# USB-UART.net
KiCad netlist of a schematic drawn in Altium Designer
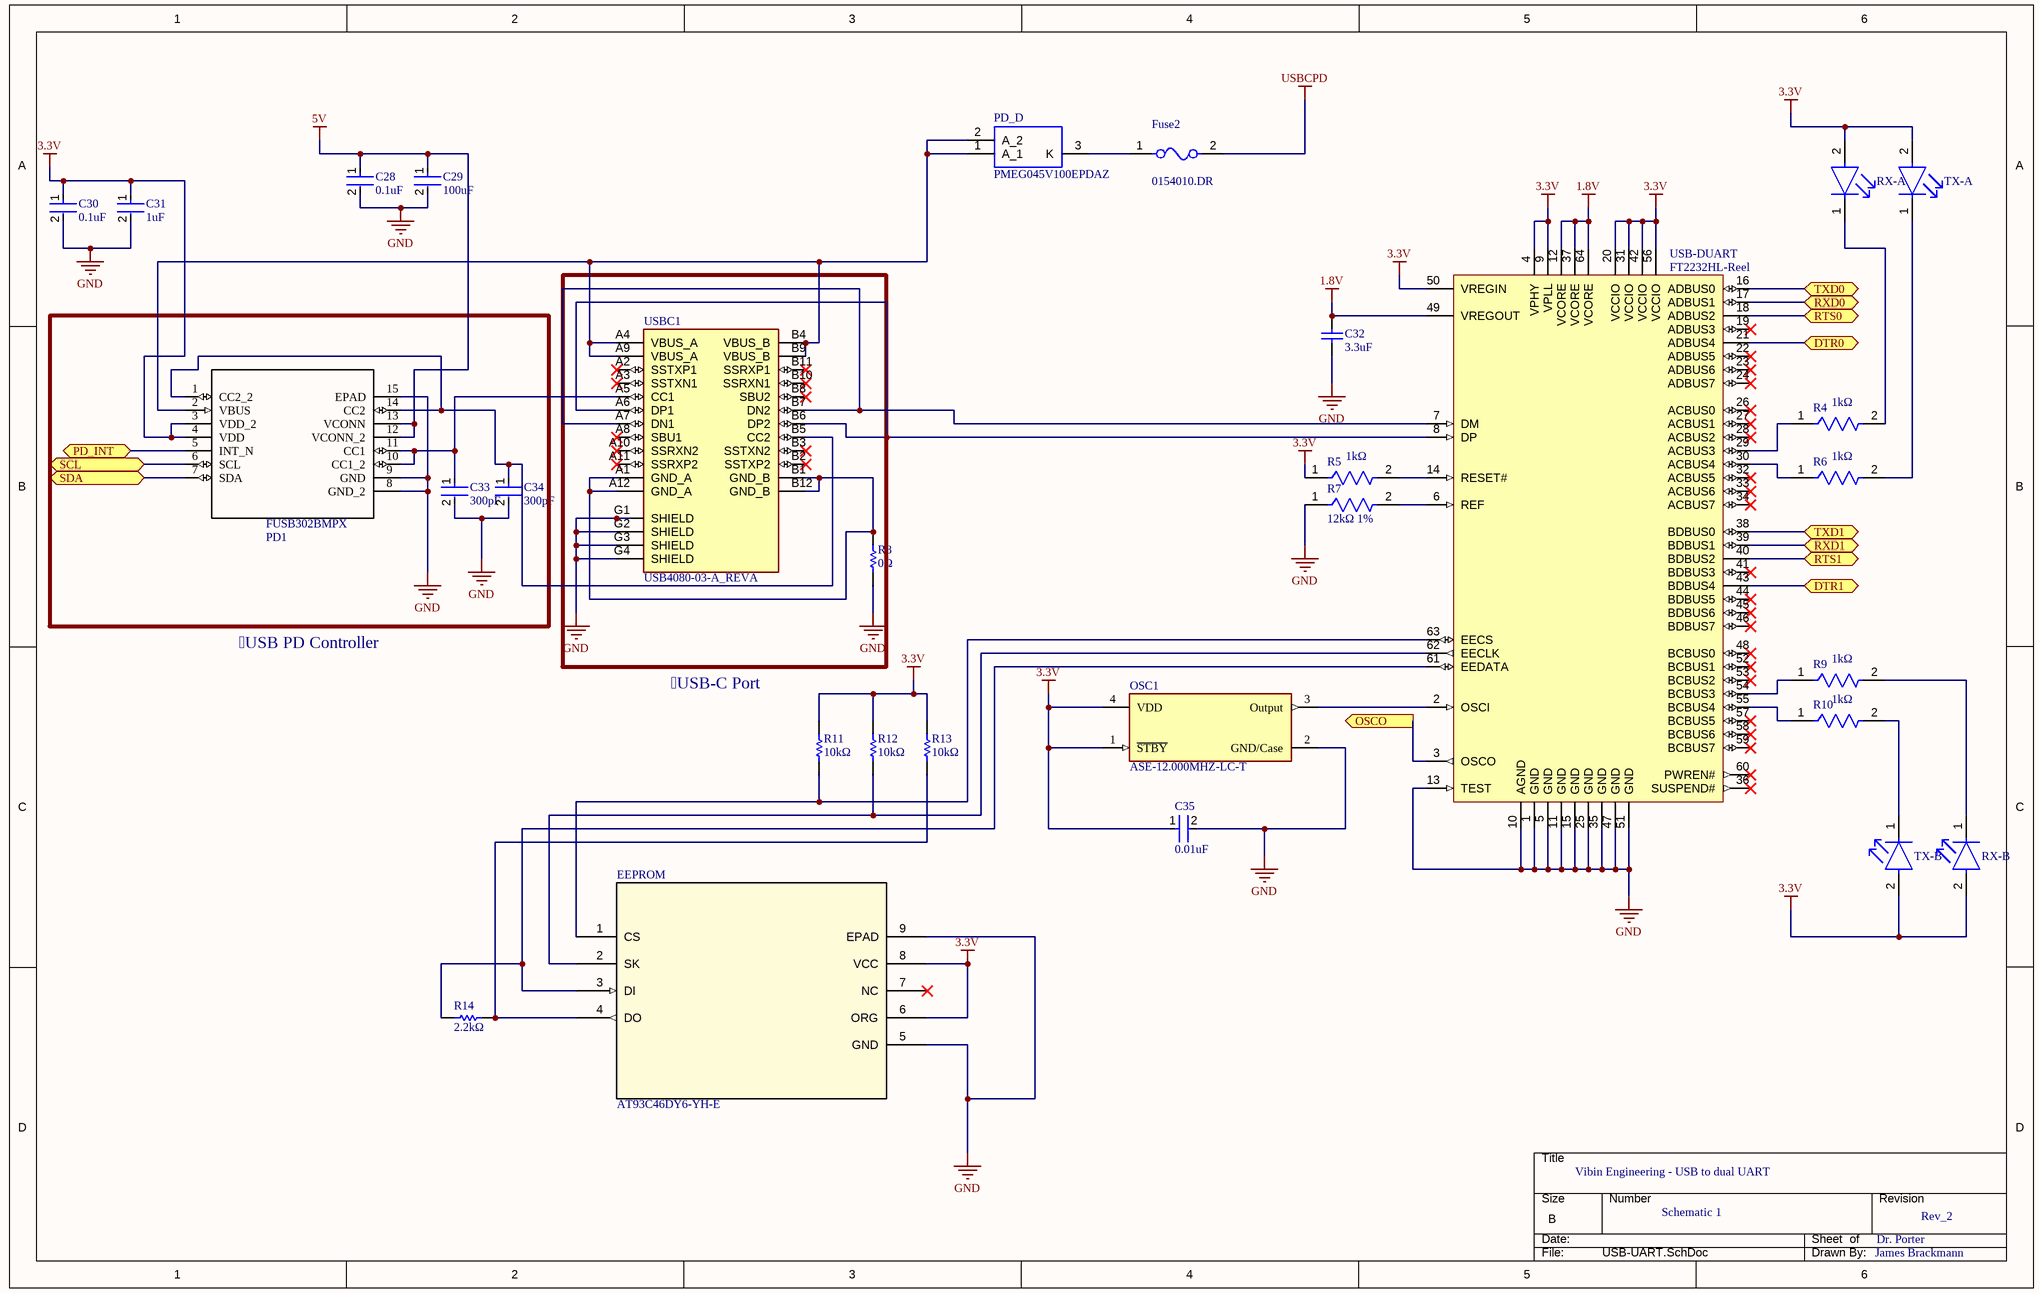
[diagram p0: USB-UART.SchDoc]

(export (version "E")
  (design (tool "Eeschema 10.0.6"))
  (components
    (comp (ref "C28")
      (value "0.1uF")
      (footprint "FP-C0603-CJ-MFG")
      (description "CAP CER 0.1UF 50V X7R 0603              C0603X104K5RACTU")
      (fields (field (name "MANUFACTURER PART NUMBER") "C0603X104K5RACTU") (field (name "VOLTAGE") "50V"))
      (libsource (lib "Altium Content Vault") (part "11868f565c42a9108669ba33697ecf6"))
    )
    (comp (ref "C29")
      (value "100uF")
      (footprint "FP-GRM32E-0_3-0_2-IPC_B")
      (fields (field (name "TOLERANCE") "20%") (field (name "VOLTAGE") "10V"))
      (libsource (lib "Altium Content Vault") (part "02cd4be3c70576c341d710602a673aa"))
    )
    (comp (ref "C30")
      (value "0.1uF")
      (footprint "FP-C0603-CJ-MFG")
      (description "CAP CER 0.1UF 50V X7R 0603              C0603X104K5RACTU")
      (fields (field (name "MANUFACTURER PART NUMBER") "C0603X104K5RACTU") (field (name "VOLTAGE") "50V"))
      (libsource (lib "Altium Content Vault") (part "11868f565c42a9108669ba33697ecf6"))
    )
    (comp (ref "C31")
      (value "1uF")
      (footprint "FP-C2012-125-0_2-IPC_A")
      (description "Multilayer Ceramic Capacitors 1μF ±10% 25V X5R SMD 0805           C2012X5R1E105K125AA")
      (fields (field (name "VOLTAGE") "25V") (field (name "TOLERANCE") "10%"))
      (libsource (lib "Altium Content Vault") (part "b4654b650e69147ec39a6b967a45e02"))
    )
    (comp (ref "C32")
      (value "3.3uF")
      (footprint "CAPC1210(3225)190_N")
      (description "CAP 3.3uF 50V ±10% 1210 (3225 Metric) Thickness 1.9mm SMD")
      (fields (field (name "TOLERANCE") "Â±10%"))
      (libsource (lib "Altium Content Vault") (part "CAP"))
    )
    (comp (ref "C33")
      (value "300pF")
      (footprint "FP-C0603C-CF-MFG")
      (description "CAP CER 300PF 50V 5% NP0 0603        C0603C301J5GACTU")
      (fields
        (field (name "TOLERANCE") "0.05")
        (field (name "OCTOPART") "https://octopart.com/c0603c301j5gactu-kemet-9143916")
      )
      (libsource (lib "Altium Content Vault") (part "b4654b650e69147ec39a6b967a45e02"))
    )
    (comp (ref "C34")
      (value "300pF")
      (footprint "FP-C0603C-CF-MFG")
      (description "CAP CER 300PF 50V 5% NP0 0603          C0603C301J5GACTU")
      (fields
        (field (name "TOLERANCE") "0.05")
        (field (name "OCTOPART") "https://octopart.com/c0603c301j5gactu-kemet-9143916")
      )
      (libsource (lib "Altium Content Vault") (part "b4654b650e69147ec39a6b967a45e02"))
    )
    (comp (ref "C35")
      (value "0.01uF")
      (footprint "FP-GRM219-0_1-IPC_B")
      (description "Chip Multilayer Ceramic Capacitors for General Purpose, 0805, 10000pF, C0G, 30ppm/°C, 5%, 50V")
      (fields (field (name "VOLTAGE") "50V") (field (name "TOLERANCE") "5%"))
      (libsource (lib "Altium Content Vault") (part "02cd4be3c70576c341d710602a673aa"))
    )
    (comp (ref "EEPROM")
      (value "AT93C46DY6-YH-E")
      (footprint "8Y6_MCH")
      (description "No Description Available")
      (fields (field (name "COPYRIGHT") "Copyright (C) 2022 Ultra Librarian. All rights reserved."))
      (libsource (lib "AT93C46DY6-YH-E") (part "AT93C46DY6-YH-E"))
    )
    (comp (ref "Fuse2")
      (value "0154010.DR")
      (footprint "FP-0154-MFG")
      (description "FUSE BRD MNT 10A 125VAC/VDC SMD    0154010.DR")
      (fields
        (field (name "MANUFACTURER") "Littelfuse Inc")
        (field (name "OCTOPART") "https://octopart.com/0154010.dr-littelfuse-565890")
      )
      (libsource (lib "Altium Content Vault") (part "5bcf9b9f640e542cf0359d10258e979"))
    )
    (comp (ref "OSC1")
      (value "ASE-12.000MHZ-LC-T")
      (footprint "FP-ASE-MFG")
      (description "XTAL Oscillator 12MHz ±50ppm CMOS 3.3V 4-SMD 3.2mm x 2.5mm")
      (libsource (lib "Altium Content Vault") (part "61a724e6190563596ac712fef61ad37"))
    )
    (comp (ref "PD1")
      (value "FUSB302BMPX")
      (footprint "*MLP14_2P5X2P5_ONS")
      (description "USB Controller USB 3.1 USB Interface 14-MLP (2.5x2.5)          FUSB302BMPX")
      (fields (field (name "MF") "ON Semiconductor"))
      (libsource (lib "FUSB302BMPX") (part "FUSB302BMPX"))
    )
    (comp (ref "PD_D")
      (value "PMEG045V100EPDAZ")
      (footprint "PMEG045V150EPDAZ")
      (description "Diode Schottky 45V 10A Surface Mount CFP15         PMEG045V100EPDAZ")
      (fields (field (name "MF") "Nexperia USA"))
      (libsource (lib "PMEG045V100EPDAZ") (part "PMEG045V100EPDAZ"))
    )
    (comp (ref "R4")
      (value "1kΩ")
      (footprint "FP-CRCW0603-e3-MFG")
      (description "RES Thick Film, 1kΩ, 1%, 0.1W, 100ppm/°C, 0603")
      (fields (field (name "TOLERANCE") "1%"))
      (libsource (lib "Altium Content Vault") (part "1029c3af85768c4190bb7ad29bc67b5"))
    )
    (comp (ref "R5")
      (value "1kΩ")
      (footprint "FP-CRCW0603-e3-MFG")
      (description "RES Thick Film, 1kΩ, 1%, 0.1W, 100ppm/°C, 0603")
      (fields (field (name "TOLERANCE") "1%"))
      (libsource (lib "Altium Content Vault") (part "1029c3af85768c4190bb7ad29bc67b5"))
    )
    (comp (ref "R6")
      (value "1kΩ")
      (footprint "FP-CRCW0603-e3-MFG")
      (description "RES Thick Film, 1kΩ, 1%, 0.1W, 100ppm/°C, 0603")
      (fields (field (name "TOLERANCE") "1%"))
      (libsource (lib "Altium Content Vault") (part "1029c3af85768c4190bb7ad29bc67b5"))
    )
    (comp (ref "R7")
      (value "12kΩ 1%")
      (footprint "FP-CRCW0603-e3-IPC_A")
      (description "RES Thick Film, 12kΩ, 1%, 0.1W, 100ppm/°C, 0603")
      (fields (field (name "TOLERANCE") "1%"))
      (libsource (lib "Altium Content Vault") (part "1029c3af85768c4190bb7ad29bc67b5"))
    )
    (comp (ref "R8")
      (value "0Ω")
      (footprint "RESC2013X50X30LL20T20")
      (description "0 kΩ for Ground of USB-C to ground plane")
      (fields (field (name "MANUFACTURER") "Vishay Dale") (field (name "PART NUMBER") "CRCW08050000Z0EA"))
      (libsource (lib "Altium Content Vault") (part "RES"))
    )
    (comp (ref "R9")
      (value "1kΩ")
      (footprint "FP-CRCW0603-e3-MFG")
      (description "RES Thick Film, 1kΩ, 1%, 0.1W, 100ppm/°C, 0603")
      (fields (field (name "TOLERANCE") "1%"))
      (libsource (lib "Altium Content Vault") (part "1029c3af85768c4190bb7ad29bc67b5"))
    )
    (comp (ref "R10")
      (value "1kΩ")
      (footprint "FP-CRCW0603-e3-MFG")
      (description "RES Thick Film, 1kΩ, 1%, 0.1W, 100ppm/°C, 0603")
      (fields (field (name "TOLERANCE") "1%"))
      (libsource (lib "Altium Content Vault") (part "1029c3af85768c4190bb7ad29bc67b5"))
    )
    (comp (ref "R11")
      (value "10kΩ")
      (footprint "RESC1005X40X25LL05T10")
      (description "RC0402FR-0710KL")
      (fields (field (name "MANUFACTURER") "Yageo / Phycomp"))
      (libsource (lib "Altium Content Vault") (part "RES"))
    )
    (comp (ref "R12")
      (value "10kΩ")
      (footprint "RESC1005X40X25LL05T10")
      (description "RC0402FR-0710KL")
      (fields (field (name "MANUFACTURER") "Yageo / Phycomp"))
      (libsource (lib "Altium Content Vault") (part "RES"))
    )
    (comp (ref "R13")
      (value "10kΩ")
      (footprint "RESC1005X40X25LL05T10")
      (description "RC0402FR-0710KL")
      (fields (field (name "MANUFACTURER") "Yageo / Phycomp"))
      (libsource (lib "Altium Content Vault") (part "RES"))
    )
    (comp (ref "R14")
      (value "2.2kΩ")
      (footprint "RESC2013X60X40NL20T25")
      (description "ERA-6AED222V")
      (fields (field (name "MANUFACTURER") "Panasonic"))
      (libsource (lib "Altium Content Vault") (part "RES"))
    )
    (comp (ref "RX-A")
      (value "LTST-C190GKT")
      (footprint "FP-LTST-C190GKT-MFG")
      (description "LED GREEN CLEAR CHIP SMD       LTST-C190GKT")
      (fields (field (name "VOLTAGE") "2V"))
      (libsource (lib "Altium Content Vault") (part "8706943c75ba83719d021d2fdc84c58"))
    )
    (comp (ref "RX-B")
      (value "LTST-C190GKT")
      (footprint "FP-LTST-C190GKT-MFG")
      (description "LED GREEN CLEAR CHIP SMD       LTST-C190GKT")
      (fields (field (name "VOLTAGE") "2V"))
      (libsource (lib "Altium Content Vault") (part "8706943c75ba83719d021d2fdc84c58"))
    )
    (comp (ref "TX-A")
      (value "LTST-C190GKT")
      (footprint "FP-LTST-C190GKT-MFG")
      (description "LED GREEN CLEAR CHIP SMD       LTST-C190GKT")
      (fields (field (name "VOLTAGE") "2V"))
      (libsource (lib "Altium Content Vault") (part "8706943c75ba83719d021d2fdc84c58"))
    )
    (comp (ref "TX-B")
      (value "LTST-C190GKT")
      (footprint "FP-LTST-C190GKT-MFG")
      (description "LED GREEN CLEAR CHIP SMD       LTST-C190GKT")
      (fields (field (name "VOLTAGE") "2V"))
      (libsource (lib "Altium Content Vault") (part "8706943c75ba83719d021d2fdc84c58"))
    )
    (comp (ref "USB-DUART")
      (value "FT2232HL-Reel")
      (footprint "FTDI-LQFP-64_M")
      (description "Dual High Speed USB To Multipurpose UART/FIFO IC, 64-pin LQFP, Tape and Reel")
      (fields (field (name "MANUFACTURER") "FTDI") (field (name "MANUFACTURER PART NUMBER") "FT2232HL-REEL"))
      (libsource (lib "VibinTest1_1") (part "CMP-0078-00023-3"))
    )
    (comp (ref "USBC1")
      (value "USB4080-03-A_REVA")
      (footprint "GCT_USB4080-03-A_REVA")
      (fields (field (name "MP") "USB4080-03-A") (field (name "MF") "Global Connector Technology"))
      (libsource (lib "USB4080-03-A_REVA") (part "USB4080-03-A_REVA"))
    )
  )
  (nets
    (net (code "1") (name "/DTR0") (class "Default")
      (node (ref "USB-DUART") (pin "21") (pinfunction "ADBUS4_21") (pintype "passive"))
    )
    (net (code "2") (name "/DTR1") (class "Default")
      (node (ref "USB-DUART") (pin "43") (pinfunction "BDBUS4_43") (pintype "passive"))
    )
    (net (code "3") (name "/OSCO") (class "Default")
      (node (ref "USB-DUART") (pin "3") (pinfunction "OSCO_3") (pintype "output"))
    )
    (net (code "4") (name "/PD_INT") (class "Default")
      (node (ref "PD1") (pin "5") (pinfunction "INT_N_5") (pintype "passive"))
    )
    (net (code "5") (name "/RTS0") (class "Default")
      (node (ref "USB-DUART") (pin "18") (pinfunction "ADBUS2_18") (pintype "passive"))
    )
    (net (code "6") (name "/RTS1") (class "Default")
      (node (ref "USB-DUART") (pin "40") (pinfunction "BDBUS2_40") (pintype "passive"))
    )
    (net (code "7") (name "/RXD0") (class "Default")
      (node (ref "USB-DUART") (pin "17") (pinfunction "ADBUS1_17") (pintype "bidirectional"))
    )
    (net (code "8") (name "/RXD1") (class "Default")
      (node (ref "USB-DUART") (pin "39") (pinfunction "BDBUS1_39") (pintype "bidirectional"))
    )
    (net (code "9") (name "/SCL") (class "Default")
      (node (ref "PD1") (pin "6") (pinfunction "SCL_6") (pintype "bidirectional"))
    )
    (net (code "10") (name "/SDA") (class "Default")
      (node (ref "PD1") (pin "7") (pinfunction "SDA_7") (pintype "bidirectional"))
    )
    (net (code "11") (name "/TXD0") (class "Default")
      (node (ref "USB-DUART") (pin "16") (pinfunction "ADBUS0_16") (pintype "bidirectional"))
    )
    (net (code "12") (name "/TXD1") (class "Default")
      (node (ref "USB-DUART") (pin "38") (pinfunction "BDBUS0_38") (pintype "bidirectional"))
    )
    (net (code "13") (name "1.8V") (class "Default")
      (node (ref "C32") (pin "2") (pinfunction "2_2") (pintype "passive"))
      (node (ref "USB-DUART") (pin "12") (pinfunction "VCORE_12") (pintype "power_in"))
      (node (ref "USB-DUART") (pin "37") (pinfunction "VCORE_37") (pintype "power_in"))
      (node (ref "USB-DUART") (pin "49") (pinfunction "VREGOUT_49") (pintype "power_in"))
      (node (ref "USB-DUART") (pin "64") (pinfunction "VCORE_64") (pintype "power_in"))
    )
    (net (code "14") (name "3.3V") (class "Default")
      (node (ref "C30") (pin "1") (pinfunction "1_1") (pintype "passive"))
      (node (ref "C31") (pin "1") (pinfunction "1_1") (pintype "passive"))
      (node (ref "C35") (pin "1") (pinfunction "1_1") (pintype "passive"))
      (node (ref "EEPROM") (pin "6") (pinfunction "ORG_6") (pintype "power_in"))
      (node (ref "EEPROM") (pin "8") (pinfunction "VCC_8") (pintype "power_in"))
      (node (ref "OSC1") (pin "1") (pinfunction "~{STBY}_1") (pintype "input"))
      (node (ref "OSC1") (pin "4") (pinfunction "VDD_4") (pintype "power_in"))
      (node (ref "PD1") (pin "3") (pinfunction "VDD_2_3") (pintype "power_in"))
      (node (ref "PD1") (pin "4") (pinfunction "VDD_4") (pintype "power_in"))
      (node (ref "R11") (pin "2") (pinfunction "2_2") (pintype "passive"))
      (node (ref "R12") (pin "2") (pinfunction "2_2") (pintype "passive"))
      (node (ref "R13") (pin "2") (pinfunction "2_2") (pintype "passive"))
      (node (ref "R5") (pin "1") (pinfunction "1_1") (pintype "passive"))
      (node (ref "RX-A") (pin "2") (pinfunction "A_2") (pintype "passive"))
      (node (ref "RX-B") (pin "2") (pinfunction "A_2") (pintype "passive"))
      (node (ref "TX-A") (pin "2") (pinfunction "A_2") (pintype "passive"))
      (node (ref "TX-B") (pin "2") (pinfunction "A_2") (pintype "passive"))
      (node (ref "USB-DUART") (pin "20") (pinfunction "VCCIO_20") (pintype "power_in"))
      (node (ref "USB-DUART") (pin "31") (pinfunction "VCCIO_31") (pintype "power_in"))
      (node (ref "USB-DUART") (pin "4") (pinfunction "VPHY_4") (pintype "power_in"))
      (node (ref "USB-DUART") (pin "42") (pinfunction "VCCIO_42") (pintype "power_in"))
      (node (ref "USB-DUART") (pin "50") (pinfunction "VREGIN_50") (pintype "power_in"))
      (node (ref "USB-DUART") (pin "56") (pinfunction "VCCIO_56") (pintype "power_in"))
      (node (ref "USB-DUART") (pin "9") (pinfunction "VPLL_9") (pintype "power_in"))
    )
    (net (code "15") (name "5V") (class "Default")
      (node (ref "C28") (pin "1") (pinfunction "1_1") (pintype "passive"))
      (node (ref "C29") (pin "1") (pinfunction "1_1") (pintype "passive"))
      (node (ref "PD1") (pin "12") (pinfunction "VCONN_2_12") (pintype "power_in"))
      (node (ref "PD1") (pin "13") (pinfunction "VCONN_13") (pintype "power_in"))
    )
    (net (code "16") (name "GND") (class "Default")
      (node (ref "C28") (pin "2") (pinfunction "2_2") (pintype "passive"))
      (node (ref "C29") (pin "2") (pinfunction "2_2") (pintype "passive"))
      (node (ref "C30") (pin "2") (pinfunction "2_2") (pintype "passive"))
      (node (ref "C31") (pin "2") (pinfunction "2_2") (pintype "passive"))
      (node (ref "C32") (pin "1") (pinfunction "1_1") (pintype "passive"))
      (node (ref "C33") (pin "2") (pinfunction "2_2") (pintype "passive"))
      (node (ref "C34") (pin "2") (pinfunction "2_2") (pintype "passive"))
      (node (ref "C35") (pin "2") (pinfunction "2_2") (pintype "passive"))
      (node (ref "EEPROM") (pin "5") (pinfunction "GND_5") (pintype "power_in"))
      (node (ref "EEPROM") (pin "9") (pinfunction "EPAD_9") (pintype "passive"))
      (node (ref "OSC1") (pin "2") (pinfunction "GND/Case_2") (pintype "power_in"))
      (node (ref "PD1") (pin "15") (pinfunction "EPAD_15") (pintype "passive"))
      (node (ref "PD1") (pin "8") (pinfunction "GND_2_8") (pintype "power_in"))
      (node (ref "PD1") (pin "9") (pinfunction "GND_9") (pintype "power_in"))
      (node (ref "R7") (pin "1") (pinfunction "1_1") (pintype "passive"))
      (node (ref "R8") (pin "1") (pinfunction "1_1") (pintype "passive"))
      (node (ref "USB-DUART") (pin "1") (pinfunction "GND_1") (pintype "power_in"))
      (node (ref "USB-DUART") (pin "10") (pinfunction "AGND_10") (pintype "power_in"))
      (node (ref "USB-DUART") (pin "11") (pinfunction "GND_11") (pintype "power_in"))
      (node (ref "USB-DUART") (pin "13") (pinfunction "TEST_13") (pintype "input"))
      (node (ref "USB-DUART") (pin "15") (pinfunction "GND_15") (pintype "power_in"))
      (node (ref "USB-DUART") (pin "25") (pinfunction "GND_25") (pintype "power_in"))
      (node (ref "USB-DUART") (pin "35") (pinfunction "GND_35") (pintype "power_in"))
      (node (ref "USB-DUART") (pin "47") (pinfunction "GND_47") (pintype "power_in"))
      (node (ref "USB-DUART") (pin "5") (pinfunction "GND_5") (pintype "power_in"))
      (node (ref "USB-DUART") (pin "51") (pinfunction "GND_51") (pintype "power_in"))
      (node (ref "USBC1") (pin "G1") (pinfunction "SHIELD_G1") (pintype "passive"))
      (node (ref "USBC1") (pin "G2") (pinfunction "SHIELD_G2") (pintype "passive"))
      (node (ref "USBC1") (pin "G3") (pinfunction "SHIELD_G3") (pintype "passive"))
      (node (ref "USBC1") (pin "G4") (pinfunction "SHIELD_G4") (pintype "passive"))
    )
    (net (code "17") (name "Net-(EEPROM-CS)") (class "Default")
      (node (ref "EEPROM") (pin "1") (pinfunction "CS_1") (pintype "passive"))
      (node (ref "R11") (pin "1") (pinfunction "1_1") (pintype "passive"))
      (node (ref "USB-DUART") (pin "63") (pinfunction "EECS_63") (pintype "bidirectional"))
    )
    (net (code "18") (name "Net-(EEPROM-DI)") (class "Default")
      (node (ref "EEPROM") (pin "3") (pinfunction "DI_3") (pintype "input"))
      (node (ref "R14") (pin "1") (pinfunction "1_1") (pintype "passive"))
      (node (ref "USB-DUART") (pin "61") (pinfunction "EEDATA_61") (pintype "bidirectional"))
    )
    (net (code "19") (name "Net-(EEPROM-DO)") (class "Default")
      (node (ref "EEPROM") (pin "4") (pinfunction "DO_4") (pintype "output"))
      (node (ref "R13") (pin "1") (pinfunction "1_1") (pintype "passive"))
      (node (ref "R14") (pin "2") (pinfunction "2_2") (pintype "passive"))
    )
    (net (code "20") (name "Net-(EEPROM-SK)") (class "Default")
      (node (ref "EEPROM") (pin "2") (pinfunction "SK_2") (pintype "passive"))
      (node (ref "R12") (pin "1") (pinfunction "1_1") (pintype "passive"))
      (node (ref "USB-DUART") (pin "62") (pinfunction "EECLK_62") (pintype "output"))
    )
    (net (code "21") (name "Net-(OSC1-Output)") (class "Default")
      (node (ref "OSC1") (pin "3") (pinfunction "Output_3") (pintype "output"))
      (node (ref "USB-DUART") (pin "2") (pinfunction "OSCI_2") (pintype "input"))
    )
    (net (code "22") (name "Net-(PD1-CC1)") (class "Default")
      (node (ref "C33") (pin "1") (pinfunction "1_1") (pintype "passive"))
      (node (ref "PD1") (pin "10") (pinfunction "CC1_2_10") (pintype "bidirectional"))
      (node (ref "PD1") (pin "11") (pinfunction "CC1_11") (pintype "bidirectional"))
      (node (ref "USBC1") (pin "A5") (pinfunction "CC1_A5") (pintype "bidirectional"))
    )
    (net (code "23") (name "Net-(PD1-CC2)") (class "Default")
      (node (ref "C34") (pin "1") (pinfunction "1_1") (pintype "passive"))
      (node (ref "PD1") (pin "1") (pinfunction "CC2_2_1") (pintype "bidirectional"))
      (node (ref "PD1") (pin "14") (pinfunction "CC2_14") (pintype "bidirectional"))
      (node (ref "USBC1") (pin "B5") (pinfunction "CC2_B5") (pintype "bidirectional"))
    )
    (net (code "24") (name "Net-(PD1-VBUS)") (class "Default")
      (node (ref "PD1") (pin "2") (pinfunction "VBUS_2") (pintype "input"))
      (node (ref "PD_D") (pin "1") (pinfunction "A_1_1") (pintype "passive"))
      (node (ref "PD_D") (pin "2") (pinfunction "A_2_2") (pintype "passive"))
      (node (ref "USBC1") (pin "A4") (pinfunction "VBUS_A_A4") (pintype "power_in"))
      (node (ref "USBC1") (pin "A9") (pinfunction "VBUS_A_A9") (pintype "power_in"))
      (node (ref "USBC1") (pin "B4") (pinfunction "VBUS_B_B4") (pintype "power_in"))
      (node (ref "USBC1") (pin "B9") (pinfunction "VBUS_B_B9") (pintype "power_in"))
    )
    (net (code "25") (name "Net-(PD_D-K)") (class "Default")
      (node (ref "Fuse2") (pin "1") (pinfunction "1_1") (pintype "passive"))
      (node (ref "PD_D") (pin "3") (pinfunction "K_3") (pintype "passive"))
    )
    (net (code "26") (name "Net-(R8-Pad2)") (class "Default")
      (node (ref "R8") (pin "2") (pinfunction "2_2") (pintype "passive"))
      (node (ref "USBC1") (pin "A1") (pinfunction "GND_A_A1") (pintype "power_in"))
      (node (ref "USBC1") (pin "A12") (pinfunction "GND_A_A12") (pintype "power_in"))
      (node (ref "USBC1") (pin "B1") (pinfunction "GND_B_B1") (pintype "power_in"))
      (node (ref "USBC1") (pin "B12") (pinfunction "GND_B_B12") (pintype "power_in"))
    )
    (net (code "27") (name "Net-(RX-A-C)") (class "Default")
      (node (ref "R4") (pin "2") (pinfunction "2_2") (pintype "passive"))
      (node (ref "RX-A") (pin "1") (pinfunction "C_1") (pintype "passive"))
    )
    (net (code "28") (name "Net-(RX-B-C)") (class "Default")
      (node (ref "R9") (pin "2") (pinfunction "2_2") (pintype "passive"))
      (node (ref "RX-B") (pin "1") (pinfunction "C_1") (pintype "passive"))
    )
    (net (code "29") (name "Net-(TX-A-C)") (class "Default")
      (node (ref "R6") (pin "2") (pinfunction "2_2") (pintype "passive"))
      (node (ref "TX-A") (pin "1") (pinfunction "C_1") (pintype "passive"))
    )
    (net (code "30") (name "Net-(TX-B-C)") (class "Default")
      (node (ref "R10") (pin "2") (pinfunction "2_2") (pintype "passive"))
      (node (ref "TX-B") (pin "1") (pinfunction "C_1") (pintype "passive"))
    )
    (net (code "31") (name "Net-(USB-DUART-ACBUS3)") (class "Default")
      (node (ref "R4") (pin "1") (pinfunction "1_1") (pintype "passive"))
      (node (ref "USB-DUART") (pin "29") (pinfunction "ACBUS3_29") (pintype "bidirectional"))
    )
    (net (code "32") (name "Net-(USB-DUART-ACBUS4)") (class "Default")
      (node (ref "R6") (pin "1") (pinfunction "1_1") (pintype "passive"))
      (node (ref "USB-DUART") (pin "30") (pinfunction "ACBUS4_30") (pintype "bidirectional"))
    )
    (net (code "33") (name "Net-(USB-DUART-BCBUS3)") (class "Default")
      (node (ref "R9") (pin "1") (pinfunction "1_1") (pintype "passive"))
      (node (ref "USB-DUART") (pin "54") (pinfunction "BCBUS3_54") (pintype "bidirectional"))
    )
    (net (code "34") (name "Net-(USB-DUART-BCBUS4)") (class "Default")
      (node (ref "R10") (pin "1") (pinfunction "1_1") (pintype "passive"))
      (node (ref "USB-DUART") (pin "55") (pinfunction "BCBUS4_55") (pintype "bidirectional"))
    )
    (net (code "35") (name "Net-(USB-DUART-DM)") (class "Default")
      (node (ref "USB-DUART") (pin "7") (pinfunction "DM_7") (pintype "input"))
      (node (ref "USBC1") (pin "A7") (pinfunction "DN1_A7") (pintype "bidirectional"))
      (node (ref "USBC1") (pin "B7") (pinfunction "DN2_B7") (pintype "bidirectional"))
    )
    (net (code "36") (name "Net-(USB-DUART-DP)") (class "Default")
      (node (ref "USB-DUART") (pin "8") (pinfunction "DP_8") (pintype "input"))
      (node (ref "USBC1") (pin "A6") (pinfunction "DP1_A6") (pintype "bidirectional"))
      (node (ref "USBC1") (pin "B6") (pinfunction "DP2_B6") (pintype "bidirectional"))
    )
    (net (code "37") (name "Net-(USB-DUART-REF)") (class "Default")
      (node (ref "R7") (pin "2") (pinfunction "2_2") (pintype "passive"))
      (node (ref "USB-DUART") (pin "6") (pinfunction "REF_6") (pintype "input"))
    )
    (net (code "38") (name "Net-(USB-DUART-RESET#)") (class "Default")
      (node (ref "R5") (pin "2") (pinfunction "2_2") (pintype "passive"))
      (node (ref "USB-DUART") (pin "14") (pinfunction "RESET#_14") (pintype "input"))
    )
    (net (code "39") (name "USBCPD") (class "Default")
      (node (ref "Fuse2") (pin "2") (pinfunction "2_2") (pintype "passive"))
    )
    (net (code "40") (name "unconnected-(EEPROM-NC-Pad7)") (class "Default")
      (node (ref "EEPROM") (pin "7") (pinfunction "NC_7") (pintype "passive+no_connect"))
    )
    (net (code "41") (name "unconnected-(USB-DUART-ACBUS0-Pad26)") (class "Default")
      (node (ref "USB-DUART") (pin "26") (pinfunction "ACBUS0_26") (pintype "bidirectional+no_connect"))
    )
    (net (code "42") (name "unconnected-(USB-DUART-ACBUS1-Pad27)") (class "Default")
      (node (ref "USB-DUART") (pin "27") (pinfunction "ACBUS1_27") (pintype "bidirectional+no_connect"))
    )
    (net (code "43") (name "unconnected-(USB-DUART-ACBUS2-Pad28)") (class "Default")
      (node (ref "USB-DUART") (pin "28") (pinfunction "ACBUS2_28") (pintype "bidirectional+no_connect"))
    )
    (net (code "44") (name "unconnected-(USB-DUART-ACBUS5-Pad32)") (class "Default")
      (node (ref "USB-DUART") (pin "32") (pinfunction "ACBUS5_32") (pintype "bidirectional+no_connect"))
    )
    (net (code "45") (name "unconnected-(USB-DUART-ACBUS6-Pad33)") (class "Default")
      (node (ref "USB-DUART") (pin "33") (pinfunction "ACBUS6_33") (pintype "bidirectional+no_connect"))
    )
    (net (code "46") (name "unconnected-(USB-DUART-ACBUS7-Pad34)") (class "Default")
      (node (ref "USB-DUART") (pin "34") (pinfunction "ACBUS7_34") (pintype "bidirectional+no_connect"))
    )
    (net (code "47") (name "unconnected-(USB-DUART-ADBUS3-Pad19)") (class "Default")
      (node (ref "USB-DUART") (pin "19") (pinfunction "ADBUS3_19") (pintype "bidirectional+no_connect"))
    )
    (net (code "48") (name "unconnected-(USB-DUART-ADBUS5-Pad22)") (class "Default")
      (node (ref "USB-DUART") (pin "22") (pinfunction "ADBUS5_22") (pintype "bidirectional+no_connect"))
    )
    (net (code "49") (name "unconnected-(USB-DUART-ADBUS6-Pad23)") (class "Default")
      (node (ref "USB-DUART") (pin "23") (pinfunction "ADBUS6_23") (pintype "bidirectional+no_connect"))
    )
    (net (code "50") (name "unconnected-(USB-DUART-ADBUS7-Pad24)") (class "Default")
      (node (ref "USB-DUART") (pin "24") (pinfunction "ADBUS7_24") (pintype "bidirectional+no_connect"))
    )
    (net (code "51") (name "unconnected-(USB-DUART-BCBUS0-Pad48)") (class "Default")
      (node (ref "USB-DUART") (pin "48") (pinfunction "BCBUS0_48") (pintype "bidirectional+no_connect"))
    )
    (net (code "52") (name "unconnected-(USB-DUART-BCBUS1-Pad52)") (class "Default")
      (node (ref "USB-DUART") (pin "52") (pinfunction "BCBUS1_52") (pintype "bidirectional+no_connect"))
    )
    (net (code "53") (name "unconnected-(USB-DUART-BCBUS2-Pad53)") (class "Default")
      (node (ref "USB-DUART") (pin "53") (pinfunction "BCBUS2_53") (pintype "bidirectional+no_connect"))
    )
    (net (code "54") (name "unconnected-(USB-DUART-BCBUS5-Pad57)") (class "Default")
      (node (ref "USB-DUART") (pin "57") (pinfunction "BCBUS5_57") (pintype "bidirectional+no_connect"))
    )
    (net (code "55") (name "unconnected-(USB-DUART-BCBUS6-Pad58)") (class "Default")
      (node (ref "USB-DUART") (pin "58") (pinfunction "BCBUS6_58") (pintype "bidirectional+no_connect"))
    )
    (net (code "56") (name "unconnected-(USB-DUART-BCBUS7-Pad59)") (class "Default")
      (node (ref "USB-DUART") (pin "59") (pinfunction "BCBUS7_59") (pintype "bidirectional+no_connect"))
    )
    (net (code "57") (name "unconnected-(USB-DUART-BDBUS3-Pad41)") (class "Default")
      (node (ref "USB-DUART") (pin "41") (pinfunction "BDBUS3_41") (pintype "bidirectional+no_connect"))
    )
    (net (code "58") (name "unconnected-(USB-DUART-BDBUS5-Pad44)") (class "Default")
      (node (ref "USB-DUART") (pin "44") (pinfunction "BDBUS5_44") (pintype "bidirectional+no_connect"))
    )
    (net (code "59") (name "unconnected-(USB-DUART-BDBUS6-Pad45)") (class "Default")
      (node (ref "USB-DUART") (pin "45") (pinfunction "BDBUS6_45") (pintype "bidirectional+no_connect"))
    )
    (net (code "60") (name "unconnected-(USB-DUART-BDBUS7-Pad46)") (class "Default")
      (node (ref "USB-DUART") (pin "46") (pinfunction "BDBUS7_46") (pintype "bidirectional+no_connect"))
    )
    (net (code "61") (name "unconnected-(USB-DUART-PWREN#-Pad60)") (class "Default")
      (node (ref "USB-DUART") (pin "60") (pinfunction "PWREN#_60") (pintype "output+no_connect"))
    )
    (net (code "62") (name "unconnected-(USB-DUART-SUSPEND#-Pad36)") (class "Default")
      (node (ref "USB-DUART") (pin "36") (pinfunction "SUSPEND#_36") (pintype "output+no_connect"))
    )
    (net (code "63") (name "unconnected-(USBC1-SBU1-PadA8)") (class "Default")
      (node (ref "USBC1") (pin "A8") (pinfunction "SBU1_A8") (pintype "bidirectional+no_connect"))
    )
    (net (code "64") (name "unconnected-(USBC1-SBU2-PadB8)") (class "Default")
      (node (ref "USBC1") (pin "B8") (pinfunction "SBU2_B8") (pintype "bidirectional+no_connect"))
    )
    (net (code "65") (name "unconnected-(USBC1-SSRXN1-PadB10)") (class "Default")
      (node (ref "USBC1") (pin "B10") (pinfunction "SSRXN1_B10") (pintype "bidirectional+no_connect"))
    )
    (net (code "66") (name "unconnected-(USBC1-SSRXN2-PadA10)") (class "Default")
      (node (ref "USBC1") (pin "A10") (pinfunction "SSRXN2_A10") (pintype "bidirectional+no_connect"))
    )
    (net (code "67") (name "unconnected-(USBC1-SSRXP1-PadB11)") (class "Default")
      (node (ref "USBC1") (pin "B11") (pinfunction "SSRXP1_B11") (pintype "bidirectional+no_connect"))
    )
    (net (code "68") (name "unconnected-(USBC1-SSRXP2-PadA11)") (class "Default")
      (node (ref "USBC1") (pin "A11") (pinfunction "SSRXP2_A11") (pintype "bidirectional+no_connect"))
    )
    (net (code "69") (name "unconnected-(USBC1-SSTXN1-PadA3)") (class "Default")
      (node (ref "USBC1") (pin "A3") (pinfunction "SSTXN1_A3") (pintype "bidirectional+no_connect"))
    )
    (net (code "70") (name "unconnected-(USBC1-SSTXN2-PadB3)") (class "Default")
      (node (ref "USBC1") (pin "B3") (pinfunction "SSTXN2_B3") (pintype "bidirectional+no_connect"))
    )
    (net (code "71") (name "unconnected-(USBC1-SSTXP1-PadA2)") (class "Default")
      (node (ref "USBC1") (pin "A2") (pinfunction "SSTXP1_A2") (pintype "bidirectional+no_connect"))
    )
    (net (code "72") (name "unconnected-(USBC1-SSTXP2-PadB2)") (class "Default")
      (node (ref "USBC1") (pin "B2") (pinfunction "SSTXP2_B2") (pintype "bidirectional+no_connect"))
    )
  )
)
